# adc.net
KiCad netlist of a schematic drawn in Altium Designer
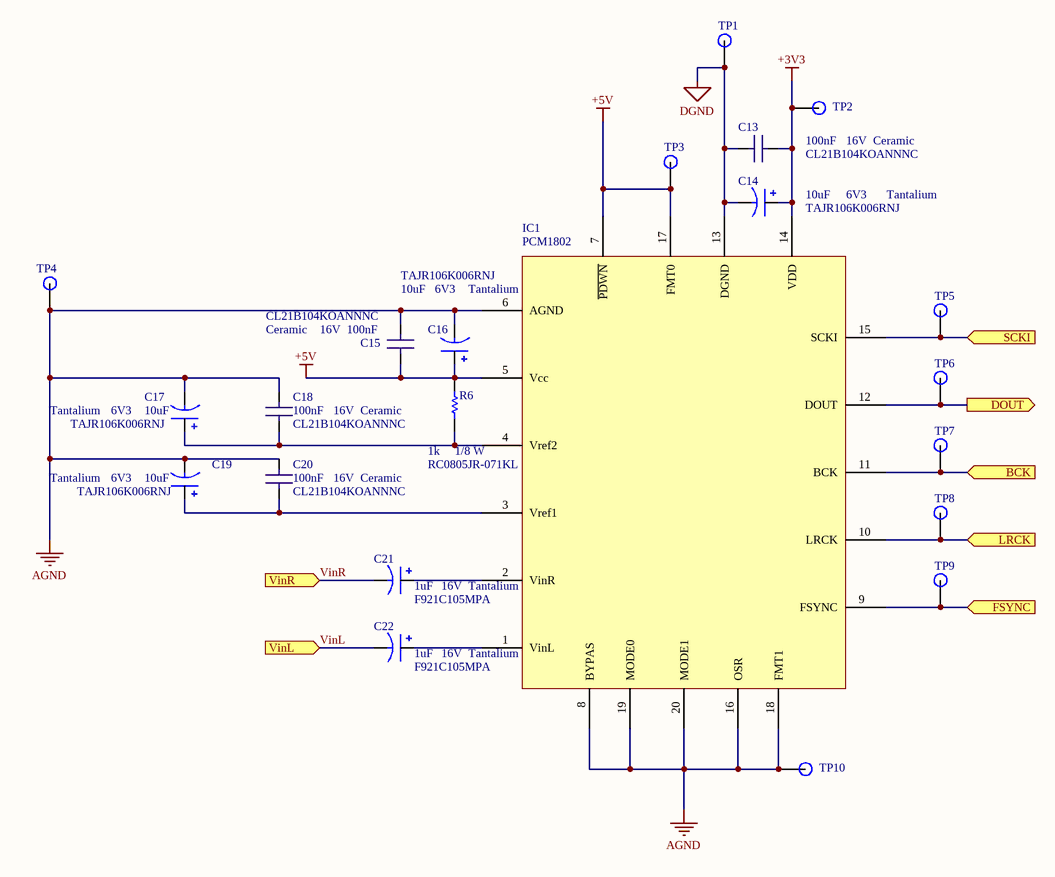
[diagram p0: adc.SchDoc]

(export (version "E")
  (design (tool "Eeschema 10.0.6"))
  (components
    (comp (ref "C13")
      (value "100nF 16V Ceramic")
      (footprint "C_0805")
      (description "Capacitor")
      (fields
        (field (name "C") "100nF")
        (field (name "V") "16V")
        (field (name "PART NUMBER") "CL21B104KOANNNC")
        (field (name "MATERIAL") "Ceramic")
      )
      (libsource (lib "TDII_Lib_V2") (part "Cap1"))
    )
    (comp (ref "C14")
      (value "10uF 6V3 Tantalium")
      (footprint "C_0805_pol")
      (description "Capacitor")
      (fields
        (field (name "C") "10uF")
        (field (name "V") "6V3")
        (field (name "MATERIAL") "Tantalium")
        (field (name "PART NUMBER") "TAJR106K006RNJ")
      )
      (libsource (lib "TDII_Lib_V2") (part "Cap_Elec"))
    )
    (comp (ref "C15")
      (value "100nF 16V Ceramic")
      (footprint "C_0805")
      (description "Capacitor")
      (fields
        (field (name "C") "100nF")
        (field (name "V") "16V")
        (field (name "PART NUMBER") "CL21B104KOANNNC")
        (field (name "MATERIAL") "Ceramic")
      )
      (libsource (lib "TDII_Lib_V2") (part "Cap1"))
    )
    (comp (ref "C16")
      (value "10uF 6V3 Tantalium")
      (footprint "C_0805_pol")
      (description "Capacitor")
      (fields
        (field (name "C") "10uF")
        (field (name "V") "6V3")
        (field (name "MATERIAL") "Tantalium")
        (field (name "PART NUMBER") "TAJR106K006RNJ")
      )
      (libsource (lib "") (part "Cap_Elec_1"))
    )
    (comp (ref "C17")
      (value "10uF 6V3 Tantalium")
      (footprint "C_0805_pol")
      (description "Capacitor")
      (fields
        (field (name "C") "10uF")
        (field (name "V") "6V3")
        (field (name "MATERIAL") "Tantalium")
        (field (name "PART NUMBER") "TAJR106K006RNJ")
      )
      (libsource (lib "") (part "Cap_Elec_1"))
    )
    (comp (ref "C18")
      (value "100nF 16V Ceramic")
      (footprint "C_0805")
      (description "Capacitor")
      (fields
        (field (name "C") "100nF")
        (field (name "V") "16V")
        (field (name "PART NUMBER") "CL21B104KOANNNC")
        (field (name "MATERIAL") "Ceramic")
      )
      (libsource (lib "TDII_Lib_V2") (part "Cap1"))
    )
    (comp (ref "C19")
      (value "10uF 6V3 Tantalium")
      (footprint "C_0805_pol")
      (description "Capacitor")
      (fields
        (field (name "C") "10uF")
        (field (name "V") "6V3")
        (field (name "MATERIAL") "Tantalium")
        (field (name "PART NUMBER") "TAJR106K006RNJ")
      )
      (libsource (lib "") (part "Cap_Elec_1"))
    )
    (comp (ref "C20")
      (value "100nF 16V Ceramic")
      (footprint "C_0805")
      (description "Capacitor")
      (fields
        (field (name "C") "100nF")
        (field (name "V") "16V")
        (field (name "PART NUMBER") "CL21B104KOANNNC")
        (field (name "MATERIAL") "Ceramic")
      )
      (libsource (lib "TDII_Lib_V2") (part "Cap1"))
    )
    (comp (ref "C21")
      (value "1uF 16V Tantalium")
      (footprint "C_0805_pol")
      (description "Capacitor")
      (fields
        (field (name "C") "1uF")
        (field (name "V") "16V")
        (field (name "MATERIAL") "Tantalium")
        (field (name "PART NUMBER") "F921C105MPA")
      )
      (libsource (lib "TDII_Lib_V2") (part "Cap_Elec"))
    )
    (comp (ref "C22")
      (value "1uF 16V Tantalium")
      (footprint "C_0805_pol")
      (description "Capacitor")
      (fields
        (field (name "C") "1uF")
        (field (name "V") "16V")
        (field (name "MATERIAL") "Tantalium")
        (field (name "PART NUMBER") "F921C105MPA")
      )
      (libsource (lib "TDII_Lib_V2") (part "Cap_Elec"))
    )
    (comp (ref "IC1")
      (value "PCM1802")
      (footprint "SSOP_DB20")
      (fields (field (name "PART NUMBER") "PCM1802DBR"))
      (libsource (lib "TDII_Lib_V2") (part "PCM1802"))
    )
    (comp (ref "R6")
      (value "1k")
      (footprint "R_0805")
      (description "Resistor")
      (fields
        (field (name "POWER") "1/8 W")
        (field (name "PART NUMBER") "RC0805JR-071KL")
        (field (name "Comment") "1k 1/8W")
      )
      (libsource (lib "TDII_Lib_V2") (part "Res1"))
    )
    (comp (ref "TP1")
      (value "TP")
      (footprint "TP")
      (description "Test Point")
      (libsource (lib "LituLib") (part "Test Point"))
    )
    (comp (ref "TP2")
      (value "TP")
      (footprint "TP")
      (description "Test Point")
      (libsource (lib "LituLib") (part "Test Point"))
    )
    (comp (ref "TP3")
      (value "TP")
      (footprint "TP")
      (description "Test Point")
      (libsource (lib "LituLib") (part "Test Point"))
    )
    (comp (ref "TP4")
      (value "TP")
      (footprint "TP")
      (description "Test Point")
      (libsource (lib "LituLib") (part "Test Point"))
    )
    (comp (ref "TP5")
      (value "TP")
      (footprint "TP")
      (description "Test Point")
      (libsource (lib "LituLib") (part "Test Point"))
    )
    (comp (ref "TP6")
      (value "TP")
      (footprint "TP")
      (description "Test Point")
      (libsource (lib "LituLib") (part "Test Point"))
    )
    (comp (ref "TP7")
      (value "TP")
      (footprint "TP")
      (description "Test Point")
      (libsource (lib "LituLib") (part "Test Point"))
    )
    (comp (ref "TP8")
      (value "TP")
      (footprint "TP")
      (description "Test Point")
      (libsource (lib "LituLib") (part "Test Point"))
    )
    (comp (ref "TP9")
      (value "TP")
      (footprint "TP")
      (description "Test Point")
      (libsource (lib "LituLib") (part "Test Point"))
    )
    (comp (ref "TP10")
      (value "TP")
      (footprint "TP")
      (description "Test Point")
      (libsource (lib "LituLib") (part "Test Point"))
    )
  )
  (nets
    (net (code "1") (name "+3V3") (class "Default")
      (node (ref "C13") (pin "2") (pinfunction "2_2") (pintype "passive"))
      (node (ref "C14") (pin "1") (pinfunction "1_1") (pintype "passive"))
      (node (ref "IC1") (pin "14") (pinfunction "VDD_14") (pintype "passive"))
      (node (ref "TP2") (pin "1") (pinfunction "1_1") (pintype "passive"))
    )
    (net (code "2") (name "+5V") (class "Default")
      (node (ref "C15") (pin "2") (pinfunction "2_2") (pintype "passive"))
      (node (ref "C16") (pin "1") (pinfunction "1_1") (pintype "passive"))
      (node (ref "IC1") (pin "17") (pinfunction "FMT0_17") (pintype "passive"))
      (node (ref "IC1") (pin "5") (pinfunction "Vcc_5") (pintype "passive"))
      (node (ref "IC1") (pin "7") (pinfunction "~{PDWN}_7") (pintype "passive"))
      (node (ref "R6") (pin "1") (pinfunction "1_1") (pintype "passive"))
      (node (ref "TP3") (pin "1") (pinfunction "1_1") (pintype "passive"))
    )
    (net (code "3") (name "/BCK") (class "Default")
      (node (ref "IC1") (pin "11") (pinfunction "BCK_11") (pintype "passive"))
      (node (ref "TP7") (pin "1") (pinfunction "1_1") (pintype "passive"))
    )
    (net (code "4") (name "/DOUT") (class "Default")
      (node (ref "IC1") (pin "12") (pinfunction "DOUT_12") (pintype "passive"))
      (node (ref "TP6") (pin "1") (pinfunction "1_1") (pintype "passive"))
    )
    (net (code "5") (name "/FSYNC") (class "Default")
      (node (ref "IC1") (pin "9") (pinfunction "FSYNC_9") (pintype "passive"))
      (node (ref "TP9") (pin "1") (pinfunction "1_1") (pintype "passive"))
    )
    (net (code "6") (name "/LRCK") (class "Default")
      (node (ref "IC1") (pin "10") (pinfunction "LRCK_10") (pintype "passive"))
      (node (ref "TP8") (pin "1") (pinfunction "1_1") (pintype "passive"))
    )
    (net (code "7") (name "/SCKI") (class "Default")
      (node (ref "IC1") (pin "15") (pinfunction "SCKI_15") (pintype "passive"))
      (node (ref "TP5") (pin "1") (pinfunction "1_1") (pintype "passive"))
    )
    (net (code "8") (name "/VinL") (class "Default")
      (node (ref "C22") (pin "2") (pinfunction "2_2") (pintype "passive"))
    )
    (net (code "9") (name "/VinR") (class "Default")
      (node (ref "C21") (pin "2") (pinfunction "2_2") (pintype "passive"))
    )
    (net (code "10") (name "AGND") (class "Default")
      (node (ref "C15") (pin "1") (pinfunction "1_1") (pintype "passive"))
      (node (ref "C16") (pin "2") (pinfunction "2_2") (pintype "passive"))
      (node (ref "C17") (pin "2") (pinfunction "2_2") (pintype "passive"))
      (node (ref "C18") (pin "1") (pinfunction "1_1") (pintype "passive"))
      (node (ref "C19") (pin "2") (pinfunction "2_2") (pintype "passive"))
      (node (ref "C20") (pin "1") (pinfunction "1_1") (pintype "passive"))
      (node (ref "IC1") (pin "16") (pinfunction "OSR_16") (pintype "passive"))
      (node (ref "IC1") (pin "18") (pinfunction "FMT1_18") (pintype "passive"))
      (node (ref "IC1") (pin "19") (pinfunction "MODE0_19") (pintype "passive"))
      (node (ref "IC1") (pin "20") (pinfunction "MODE1_20") (pintype "passive"))
      (node (ref "IC1") (pin "6") (pinfunction "AGND_6") (pintype "passive"))
      (node (ref "IC1") (pin "8") (pinfunction "BYPAS_8") (pintype "passive"))
      (node (ref "TP10") (pin "1") (pinfunction "1_1") (pintype "passive"))
      (node (ref "TP4") (pin "1") (pinfunction "1_1") (pintype "passive"))
    )
    (net (code "11") (name "DGND") (class "Default")
      (node (ref "C13") (pin "1") (pinfunction "1_1") (pintype "passive"))
      (node (ref "C14") (pin "2") (pinfunction "2_2") (pintype "passive"))
      (node (ref "IC1") (pin "13") (pinfunction "DGND_13") (pintype "passive"))
      (node (ref "TP1") (pin "1") (pinfunction "1_1") (pintype "passive"))
    )
    (net (code "12") (name "Net-(IC1-VinL)") (class "Default")
      (node (ref "C22") (pin "1") (pinfunction "1_1") (pintype "passive"))
      (node (ref "IC1") (pin "1") (pinfunction "VinL_1") (pintype "passive"))
    )
    (net (code "13") (name "Net-(IC1-VinR)") (class "Default")
      (node (ref "C21") (pin "1") (pinfunction "1_1") (pintype "passive"))
      (node (ref "IC1") (pin "2") (pinfunction "VinR_2") (pintype "passive"))
    )
    (net (code "14") (name "Net-(IC1-Vref1)") (class "Default")
      (node (ref "C19") (pin "1") (pinfunction "1_1") (pintype "passive"))
      (node (ref "C20") (pin "2") (pinfunction "2_2") (pintype "passive"))
      (node (ref "IC1") (pin "3") (pinfunction "Vref1_3") (pintype "passive"))
    )
    (net (code "15") (name "Net-(IC1-Vref2)") (class "Default")
      (node (ref "C17") (pin "1") (pinfunction "1_1") (pintype "passive"))
      (node (ref "C18") (pin "2") (pinfunction "2_2") (pintype "passive"))
      (node (ref "IC1") (pin "4") (pinfunction "Vref2_4") (pintype "passive"))
      (node (ref "R6") (pin "2") (pinfunction "2_2") (pintype "passive"))
    )
  )
)
